# teensyMotors02_upSwitch_LED.net
KiCad netlist of a schematic drawn in EAGLE
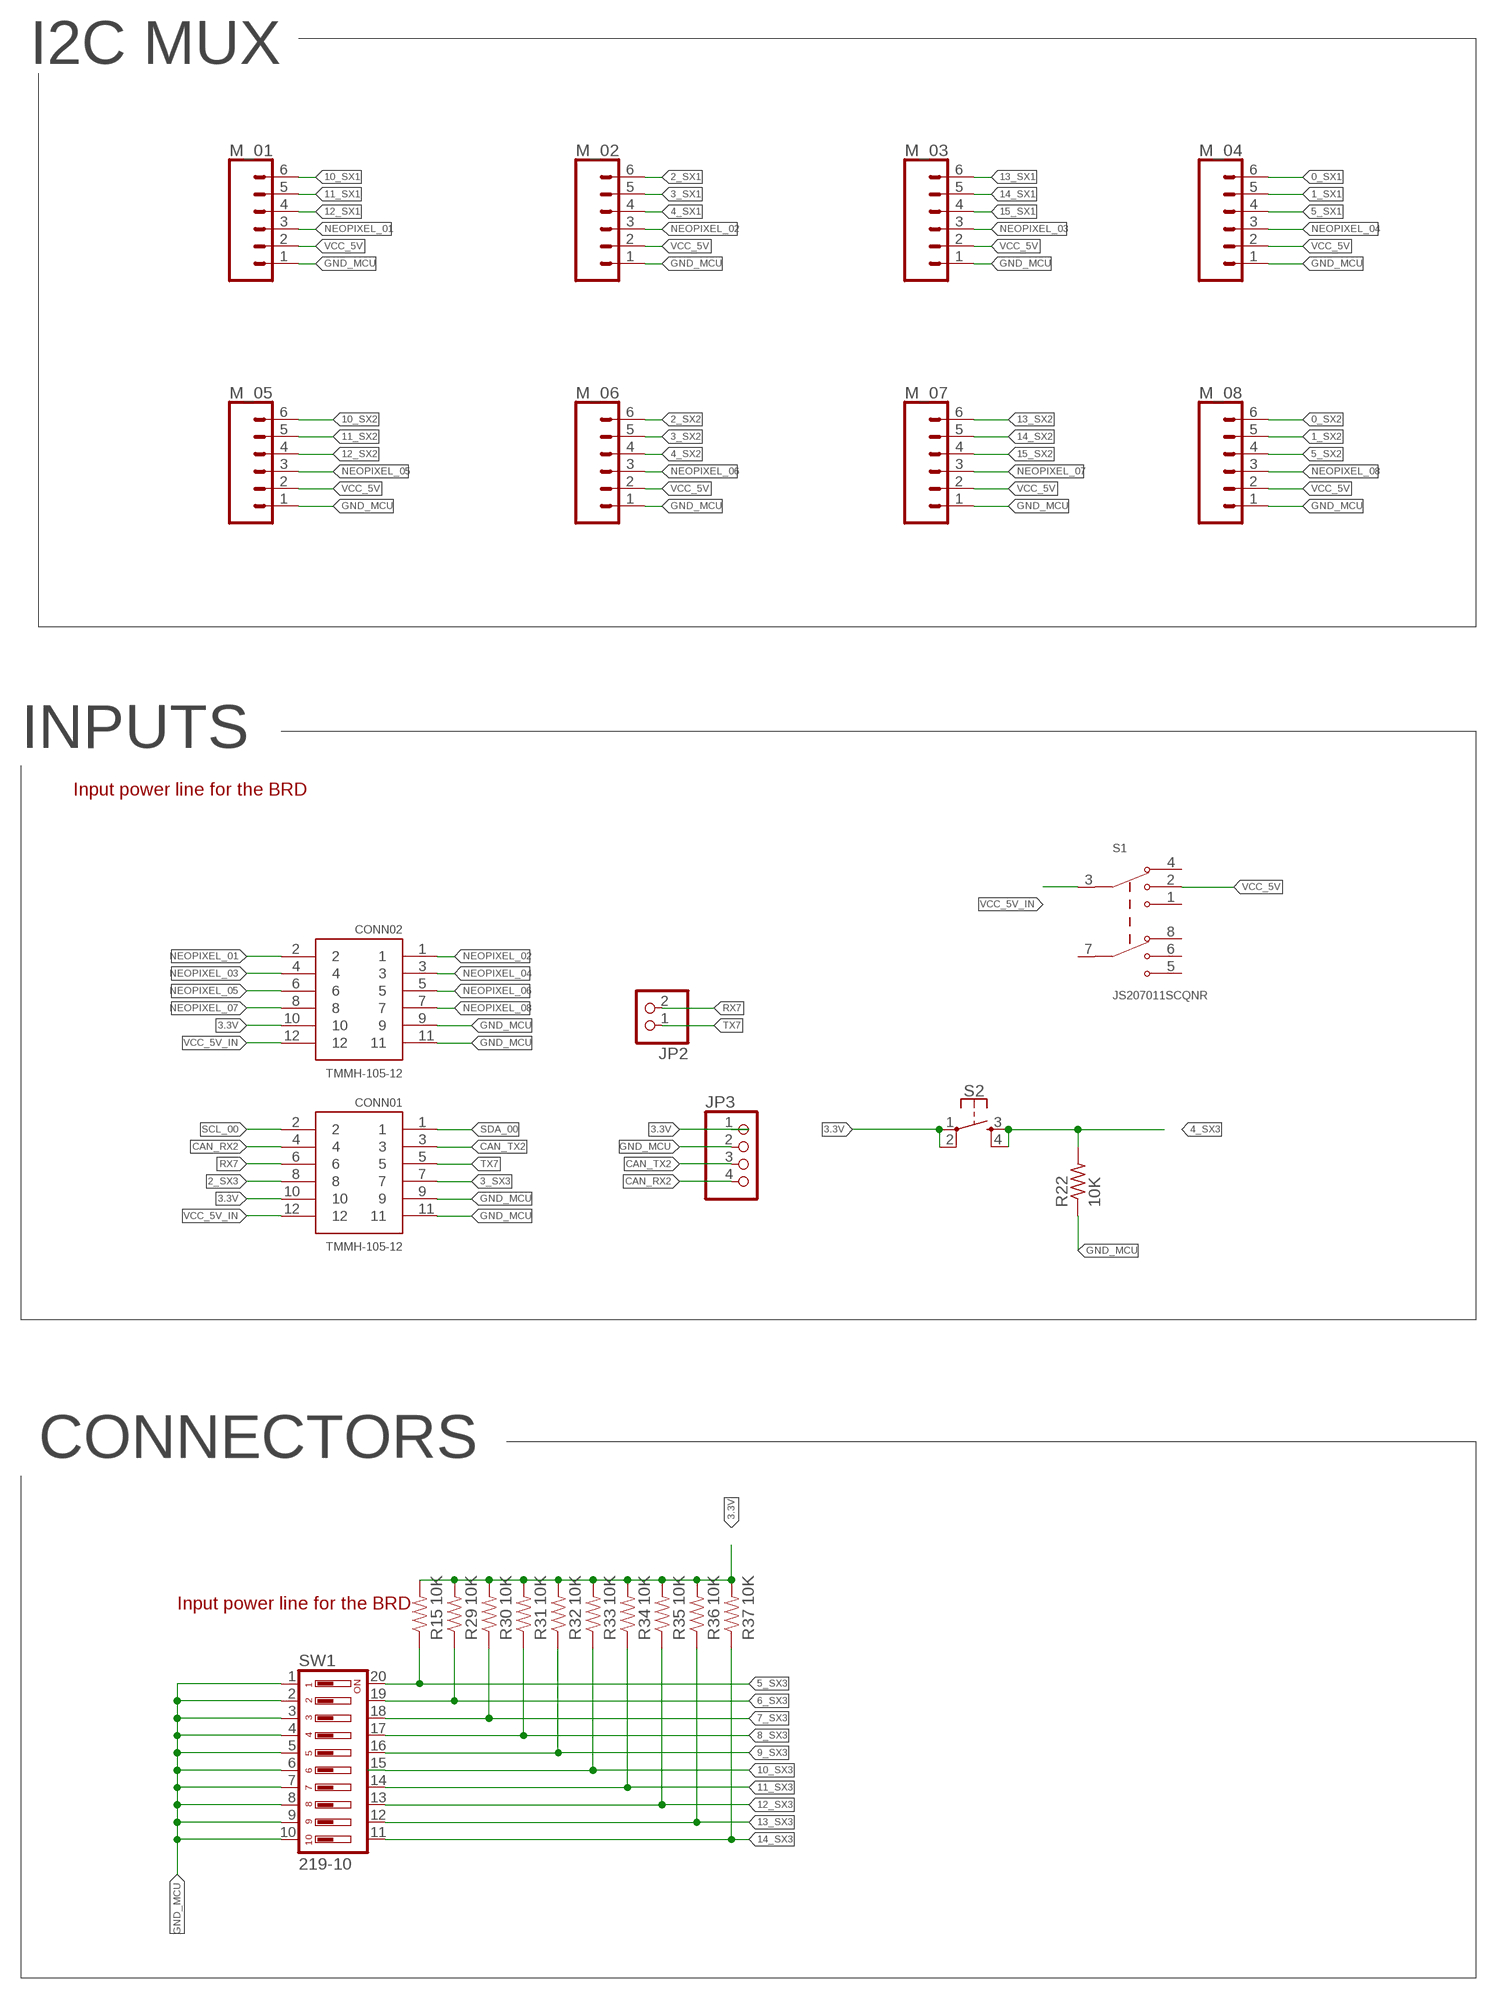
[diagram p0: schematic, sheet 1, part 1 of 3]
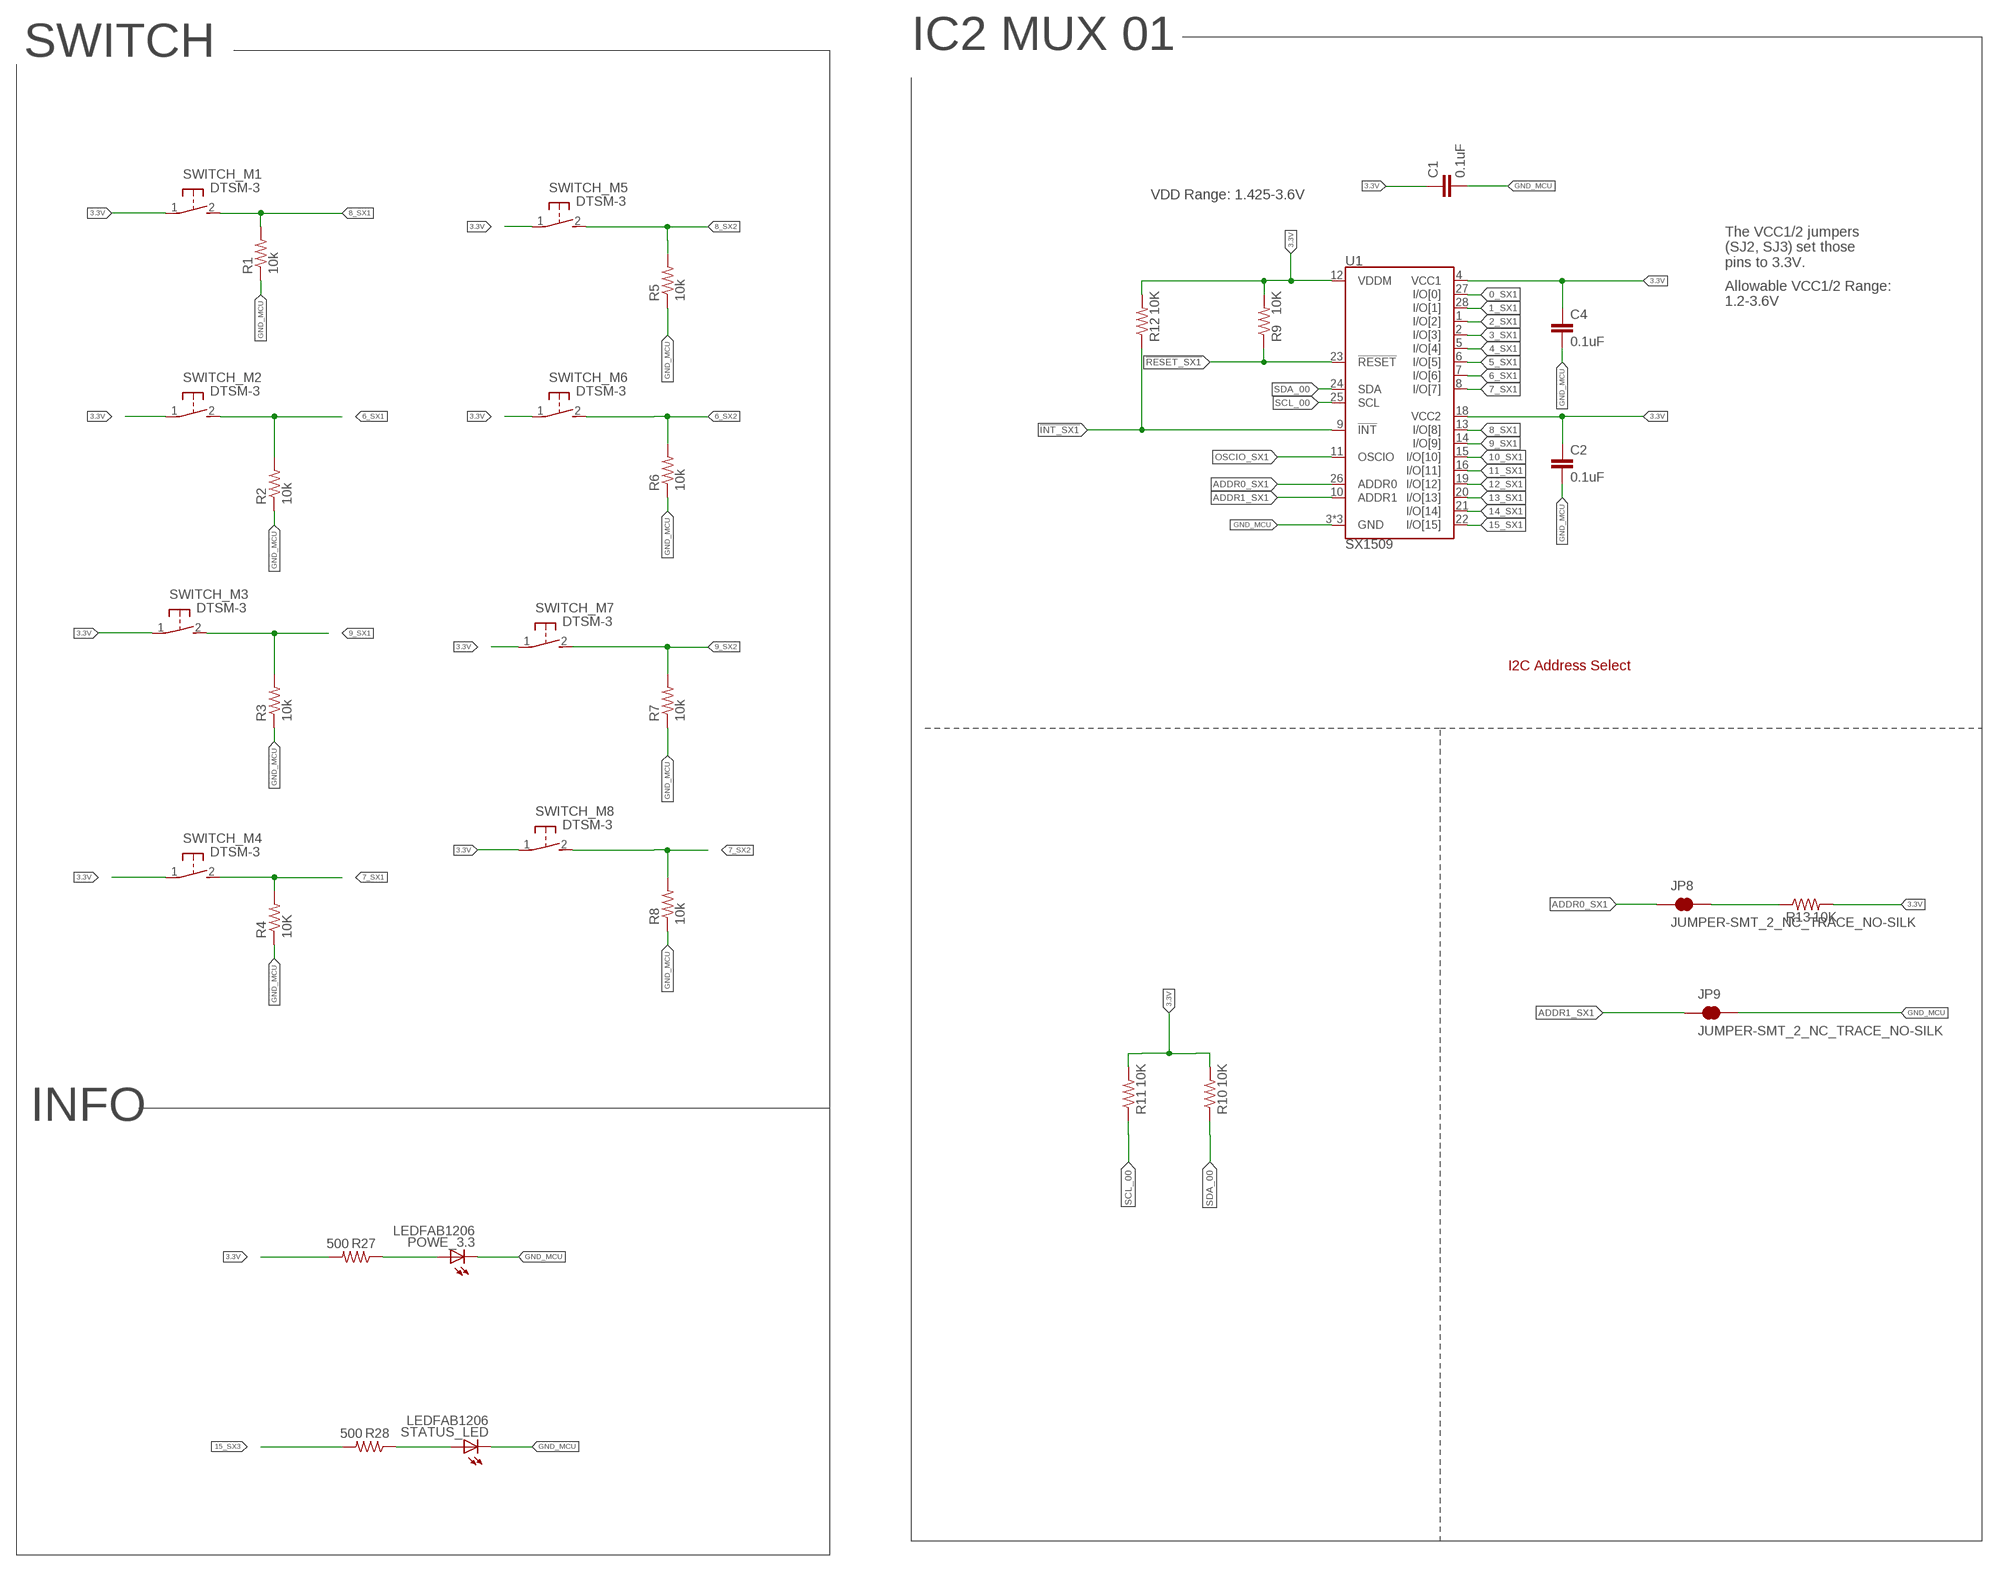
[diagram p1: schematic, sheet 1, part 2 of 3]
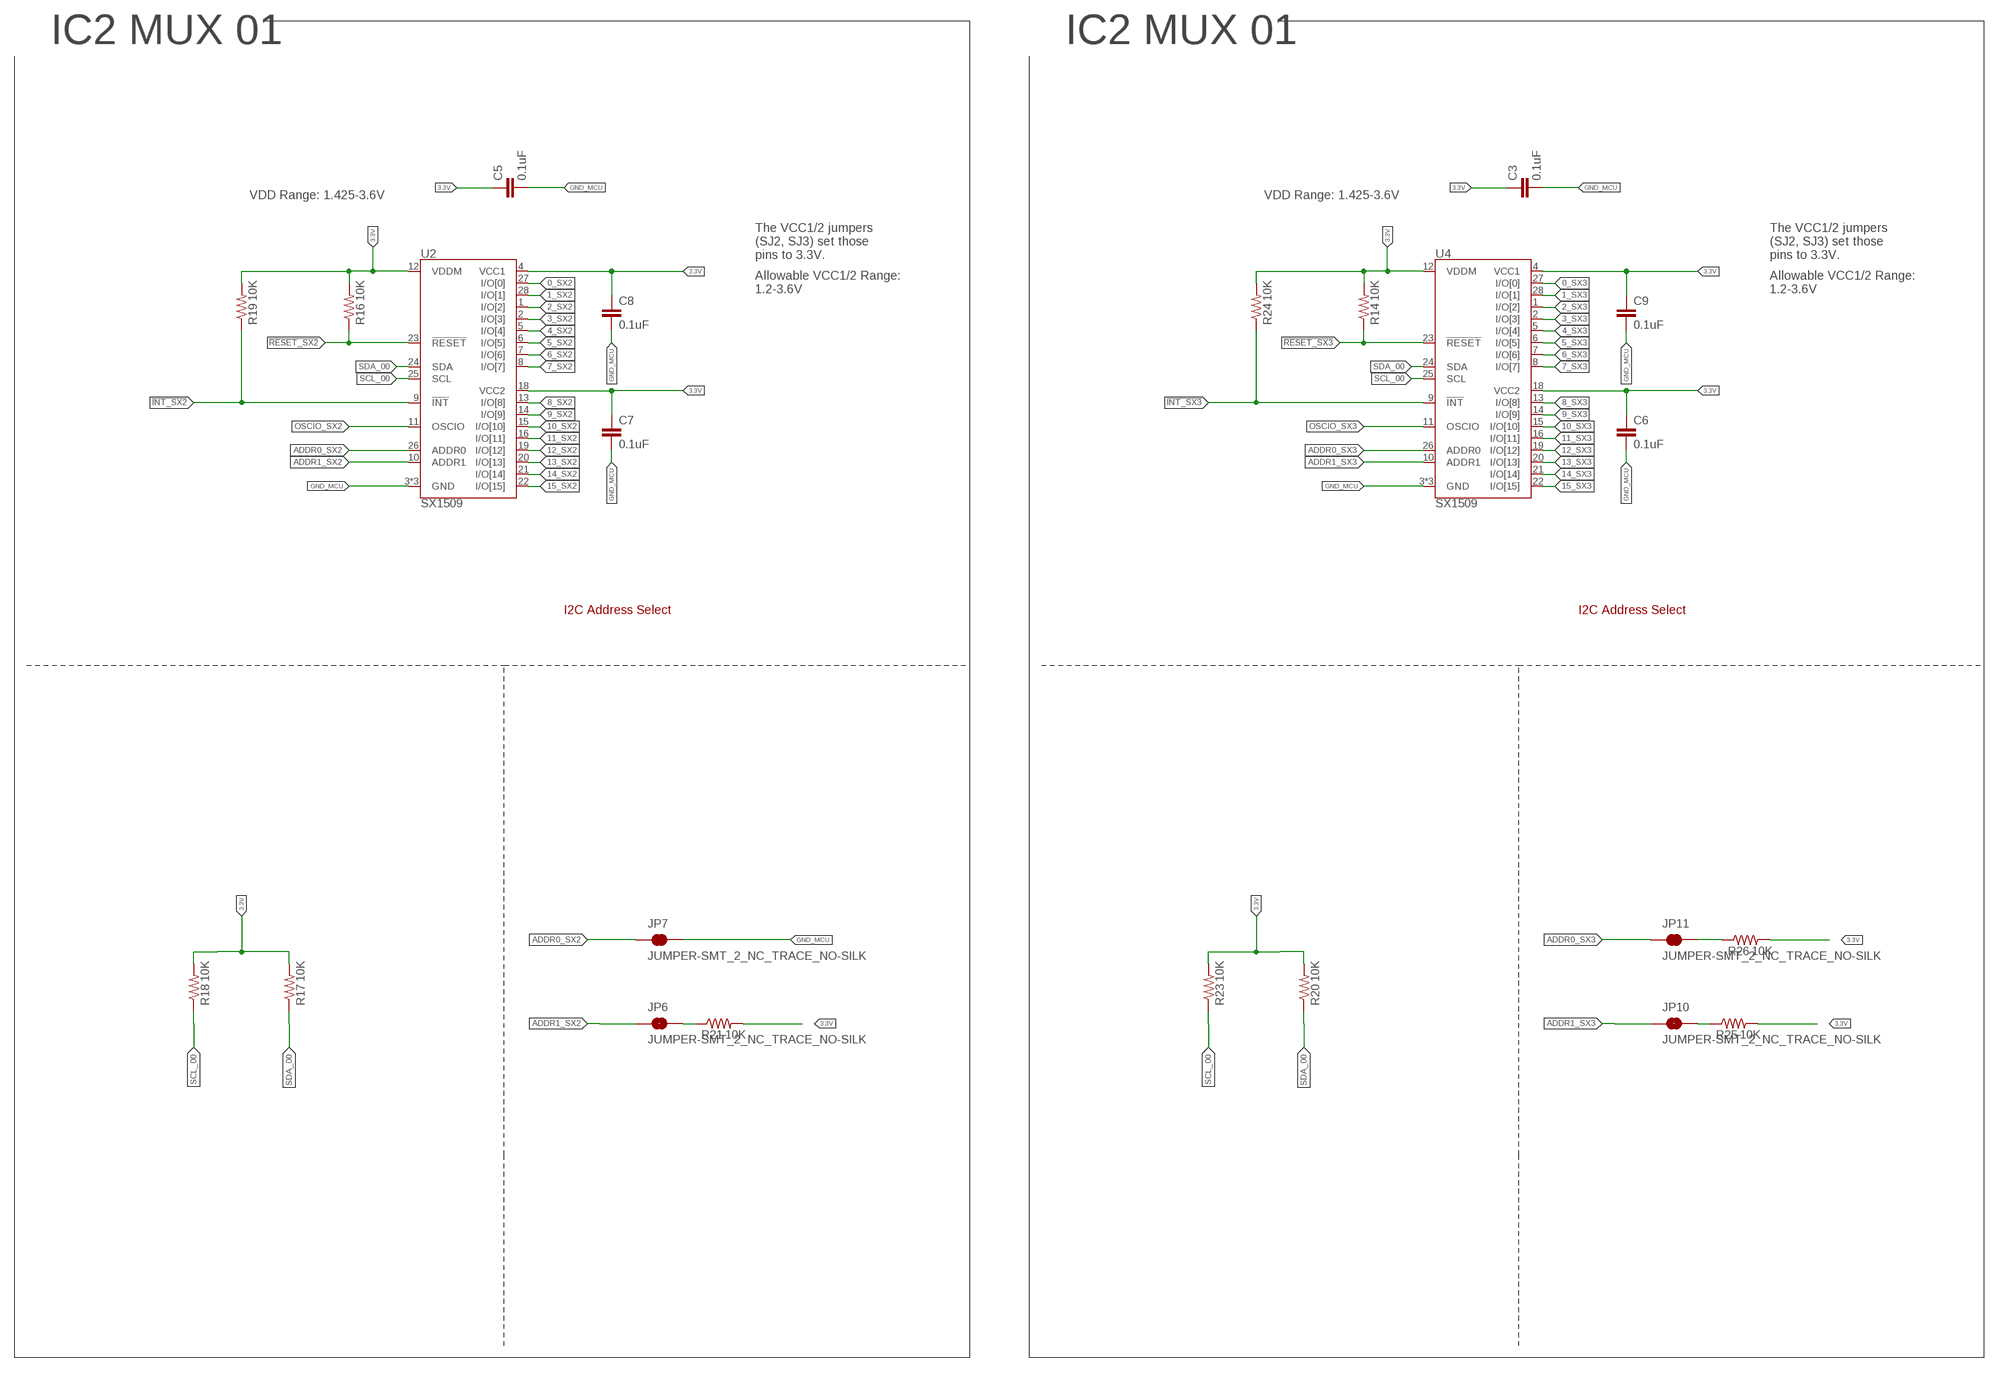
[diagram p2: schematic, sheet 1, part 3 of 3]

(export (version "E")
  (design (tool "Eeschema 10.0.6"))
  (components
    (comp (ref "C1")
      (value "0.1uF")
      (footprint "eagle-import:0603-CAP")
      (libsource (lib "eagle-import") (part "0.1UF-25V(+80/-20%)(0603)"))
    )
    (comp (ref "C2")
      (value "0.1uF")
      (footprint "eagle-import:0603-CAP")
      (libsource (lib "eagle-import") (part "0.1UF-25V(+80/-20%)(0603)"))
    )
    (comp (ref "C3")
      (value "0.1uF")
      (footprint "eagle-import:0603-CAP")
      (libsource (lib "eagle-import") (part "0.1UF-25V(+80/-20%)(0603)"))
    )
    (comp (ref "C4")
      (value "0.1uF")
      (footprint "eagle-import:0603-CAP")
      (libsource (lib "eagle-import") (part "0.1UF-25V(+80/-20%)(0603)"))
    )
    (comp (ref "C5")
      (value "0.1uF")
      (footprint "eagle-import:0603-CAP")
      (libsource (lib "eagle-import") (part "0.1UF-25V(+80/-20%)(0603)"))
    )
    (comp (ref "C6")
      (value "0.1uF")
      (footprint "eagle-import:0603-CAP")
      (libsource (lib "eagle-import") (part "0.1UF-25V(+80/-20%)(0603)"))
    )
    (comp (ref "C7")
      (value "0.1uF")
      (footprint "eagle-import:0603-CAP")
      (libsource (lib "eagle-import") (part "0.1UF-25V(+80/-20%)(0603)"))
    )
    (comp (ref "C8")
      (value "0.1uF")
      (footprint "eagle-import:0603-CAP")
      (libsource (lib "eagle-import") (part "0.1UF-25V(+80/-20%)(0603)"))
    )
    (comp (ref "C9")
      (value "0.1uF")
      (footprint "eagle-import:0603-CAP")
      (libsource (lib "eagle-import") (part "0.1UF-25V(+80/-20%)(0603)"))
    )
    (comp (ref "CONN01")
      (value "TMMH-105-12")
      (footprint "eagle-import:TMMH-105-12")
      (libsource (lib "eagle-import") (part "TMMH-105-12"))
    )
    (comp (ref "CONN02")
      (value "TMMH-105-12")
      (footprint "eagle-import:TMMH-105-12")
      (libsource (lib "eagle-import") (part "TMMH-105-12"))
    )
    (comp (ref "JP2")
      (value "HEADER-1X2ROUND")
      (footprint "eagle-import:1X02_ROUND")
      (libsource (lib "eagle-import") (part "HEADER-1X2ROUND"))
    )
    (comp (ref "JP3")
      (value "HEADER-1X4ROUND")
      (footprint "eagle-import:1X04_ROUND")
      (libsource (lib "eagle-import") (part "HEADER-1X4ROUND"))
    )
    (comp (ref "JP6")
      (value "JUMPER-SMT_2_NC_TRACE_NO-SILK")
      (footprint "eagle-import:SMT-JUMPER_2_NC_TRACE_NO-SILK")
      (libsource (lib "eagle-import") (part "JUMPER-SMT_2_NC_TRACE_NO-SILK"))
    )
    (comp (ref "JP7")
      (value "JUMPER-SMT_2_NC_TRACE_NO-SILK")
      (footprint "eagle-import:SMT-JUMPER_2_NC_TRACE_NO-SILK")
      (libsource (lib "eagle-import") (part "JUMPER-SMT_2_NC_TRACE_NO-SILK"))
    )
    (comp (ref "JP8")
      (value "JUMPER-SMT_2_NC_TRACE_NO-SILK")
      (footprint "eagle-import:SMT-JUMPER_2_NC_TRACE_NO-SILK")
      (libsource (lib "eagle-import") (part "JUMPER-SMT_2_NC_TRACE_NO-SILK"))
    )
    (comp (ref "JP9")
      (value "JUMPER-SMT_2_NC_TRACE_NO-SILK")
      (footprint "eagle-import:SMT-JUMPER_2_NC_TRACE_NO-SILK")
      (libsource (lib "eagle-import") (part "JUMPER-SMT_2_NC_TRACE_NO-SILK"))
    )
    (comp (ref "JP10")
      (value "JUMPER-SMT_2_NC_TRACE_NO-SILK")
      (footprint "eagle-import:SMT-JUMPER_2_NC_TRACE_NO-SILK")
      (libsource (lib "eagle-import") (part "JUMPER-SMT_2_NC_TRACE_NO-SILK"))
    )
    (comp (ref "JP11")
      (value "JUMPER-SMT_2_NC_TRACE_NO-SILK")
      (footprint "eagle-import:SMT-JUMPER_2_NC_TRACE_NO-SILK")
      (libsource (lib "eagle-import") (part "JUMPER-SMT_2_NC_TRACE_NO-SILK"))
    )
    (comp (ref "M_01")
      (value "CONN_06SMD-1MM")
      (footprint "eagle-import:1X06-1MM")
      (libsource (lib "eagle-import") (part "CONN_06SMD-1MM"))
    )
    (comp (ref "M_02")
      (value "CONN_06SMD-1MM")
      (footprint "eagle-import:1X06-1MM")
      (libsource (lib "eagle-import") (part "CONN_06SMD-1MM"))
    )
    (comp (ref "M_03")
      (value "CONN_06SMD-1MM")
      (footprint "eagle-import:1X06-1MM")
      (libsource (lib "eagle-import") (part "CONN_06SMD-1MM"))
    )
    (comp (ref "M_04")
      (value "CONN_06SMD-1MM")
      (footprint "eagle-import:1X06-1MM")
      (libsource (lib "eagle-import") (part "CONN_06SMD-1MM"))
    )
    (comp (ref "M_05")
      (value "CONN_06SMD-1MM")
      (footprint "eagle-import:1X06-1MM")
      (libsource (lib "eagle-import") (part "CONN_06SMD-1MM"))
    )
    (comp (ref "M_06")
      (value "CONN_06SMD-1MM")
      (footprint "eagle-import:1X06-1MM")
      (libsource (lib "eagle-import") (part "CONN_06SMD-1MM"))
    )
    (comp (ref "M_07")
      (value "CONN_06SMD-1MM")
      (footprint "eagle-import:1X06-1MM")
      (libsource (lib "eagle-import") (part "CONN_06SMD-1MM"))
    )
    (comp (ref "M_08")
      (value "CONN_06SMD-1MM")
      (footprint "eagle-import:1X06-1MM")
      (libsource (lib "eagle-import") (part "CONN_06SMD-1MM"))
    )
    (comp (ref "POWE_3.3")
      (value "LEDFAB1206")
      (footprint "eagle-import:LED1206FAB")
      (libsource (lib "eagle-import") (part "LEDFAB1206"))
    )
    (comp (ref "R1")
      (value "10k")
      (footprint "eagle-import:M0805")
      (libsource (lib "eagle-import") (part "R-US_M0805"))
    )
    (comp (ref "R2")
      (value "10k")
      (footprint "eagle-import:M0805")
      (libsource (lib "eagle-import") (part "R-US_M0805"))
    )
    (comp (ref "R3")
      (value "10k")
      (footprint "eagle-import:M0805")
      (libsource (lib "eagle-import") (part "R-US_M0805"))
    )
    (comp (ref "R4")
      (value "10K")
      (footprint "eagle-import:M0805")
      (libsource (lib "eagle-import") (part "R-US_M0805"))
    )
    (comp (ref "R5")
      (value "10k")
      (footprint "eagle-import:M0805")
      (libsource (lib "eagle-import") (part "R-US_M0805"))
    )
    (comp (ref "R6")
      (value "10k")
      (footprint "eagle-import:M0805")
      (libsource (lib "eagle-import") (part "R-US_M0805"))
    )
    (comp (ref "R7")
      (value "10k")
      (footprint "eagle-import:M0805")
      (libsource (lib "eagle-import") (part "R-US_M0805"))
    )
    (comp (ref "R8")
      (value "10k")
      (footprint "eagle-import:M0805")
      (libsource (lib "eagle-import") (part "R-US_M0805"))
    )
    (comp (ref "R9")
      (value "10K")
      (footprint "eagle-import:0603-RES")
      (libsource (lib "eagle-import") (part "SparkFun-Resistors_532_10KOHM-1/10W-1%(0603)0603"))
    )
    (comp (ref "R10")
      (value "10K")
      (footprint "eagle-import:0603-RES")
      (libsource (lib "eagle-import") (part "SparkFun-Resistors_532_10KOHM-1/10W-1%(0603)0603"))
    )
    (comp (ref "R11")
      (value "10K")
      (footprint "eagle-import:0603-RES")
      (libsource (lib "eagle-import") (part "SparkFun-Resistors_532_10KOHM-1/10W-1%(0603)0603"))
    )
    (comp (ref "R12")
      (value "10K")
      (footprint "eagle-import:0603-RES")
      (libsource (lib "eagle-import") (part "SparkFun-Resistors_532_10KOHM-1/10W-1%(0603)0603"))
    )
    (comp (ref "R13")
      (value "10K")
      (footprint "eagle-import:0603-RES")
      (libsource (lib "eagle-import") (part "SparkFun-Resistors_532_10KOHM-1/10W-1%(0603)0603"))
    )
    (comp (ref "R14")
      (value "10K")
      (footprint "eagle-import:0603-RES")
      (libsource (lib "eagle-import") (part "SparkFun-Resistors_532_10KOHM-1/10W-1%(0603)0603"))
    )
    (comp (ref "R15")
      (value "10K")
      (footprint "eagle-import:0603-RES")
      (libsource (lib "eagle-import") (part "SparkFun-Resistors_532_10KOHM-1/10W-1%(0603)0603"))
    )
    (comp (ref "R16")
      (value "10K")
      (footprint "eagle-import:0603-RES")
      (libsource (lib "eagle-import") (part "SparkFun-Resistors_532_10KOHM-1/10W-1%(0603)0603"))
    )
    (comp (ref "R17")
      (value "10K")
      (footprint "eagle-import:0603-RES")
      (libsource (lib "eagle-import") (part "SparkFun-Resistors_532_10KOHM-1/10W-1%(0603)0603"))
    )
    (comp (ref "R18")
      (value "10K")
      (footprint "eagle-import:0603-RES")
      (libsource (lib "eagle-import") (part "SparkFun-Resistors_532_10KOHM-1/10W-1%(0603)0603"))
    )
    (comp (ref "R19")
      (value "10K")
      (footprint "eagle-import:0603-RES")
      (libsource (lib "eagle-import") (part "SparkFun-Resistors_532_10KOHM-1/10W-1%(0603)0603"))
    )
    (comp (ref "R20")
      (value "10K")
      (footprint "eagle-import:0603-RES")
      (libsource (lib "eagle-import") (part "SparkFun-Resistors_532_10KOHM-1/10W-1%(0603)0603"))
    )
    (comp (ref "R21")
      (value "10K")
      (footprint "eagle-import:0603-RES")
      (libsource (lib "eagle-import") (part "SparkFun-Resistors_532_10KOHM-1/10W-1%(0603)0603"))
    )
    (comp (ref "R22")
      (value "10K")
      (footprint "eagle-import:M0805")
      (libsource (lib "eagle-import") (part "R-US_M0805"))
    )
    (comp (ref "R23")
      (value "10K")
      (footprint "eagle-import:0603-RES")
      (libsource (lib "eagle-import") (part "SparkFun-Resistors_532_10KOHM-1/10W-1%(0603)0603"))
    )
    (comp (ref "R24")
      (value "10K")
      (footprint "eagle-import:0603-RES")
      (libsource (lib "eagle-import") (part "SparkFun-Resistors_532_10KOHM-1/10W-1%(0603)0603"))
    )
    (comp (ref "R25")
      (value "10K")
      (footprint "eagle-import:0603-RES")
      (libsource (lib "eagle-import") (part "SparkFun-Resistors_532_10KOHM-1/10W-1%(0603)0603"))
    )
    (comp (ref "R26")
      (value "10K")
      (footprint "eagle-import:0603-RES")
      (libsource (lib "eagle-import") (part "SparkFun-Resistors_532_10KOHM-1/10W-1%(0603)0603"))
    )
    (comp (ref "R27")
      (value "500")
      (footprint "eagle-import:0603-RES")
      (libsource (lib "eagle-import") (part "10KOHM-1/10W-1%(0603)0603"))
    )
    (comp (ref "R28")
      (value "500")
      (footprint "eagle-import:0603-RES")
      (libsource (lib "eagle-import") (part "10KOHM-1/10W-1%(0603)0603"))
    )
    (comp (ref "R29")
      (value "10K")
      (footprint "eagle-import:0603-RES")
      (libsource (lib "eagle-import") (part "SparkFun-Resistors_532_10KOHM-1/10W-1%(0603)0603"))
    )
    (comp (ref "R30")
      (value "10K")
      (footprint "eagle-import:0603-RES")
      (libsource (lib "eagle-import") (part "SparkFun-Resistors_532_10KOHM-1/10W-1%(0603)0603"))
    )
    (comp (ref "R31")
      (value "10K")
      (footprint "eagle-import:0603-RES")
      (libsource (lib "eagle-import") (part "SparkFun-Resistors_532_10KOHM-1/10W-1%(0603)0603"))
    )
    (comp (ref "R32")
      (value "10K")
      (footprint "eagle-import:0603-RES")
      (libsource (lib "eagle-import") (part "SparkFun-Resistors_532_10KOHM-1/10W-1%(0603)0603"))
    )
    (comp (ref "R33")
      (value "10K")
      (footprint "eagle-import:0603-RES")
      (libsource (lib "eagle-import") (part "SparkFun-Resistors_532_10KOHM-1/10W-1%(0603)0603"))
    )
    (comp (ref "R34")
      (value "10K")
      (footprint "eagle-import:0603-RES")
      (libsource (lib "eagle-import") (part "SparkFun-Resistors_532_10KOHM-1/10W-1%(0603)0603"))
    )
    (comp (ref "R35")
      (value "10K")
      (footprint "eagle-import:0603-RES")
      (libsource (lib "eagle-import") (part "SparkFun-Resistors_532_10KOHM-1/10W-1%(0603)0603"))
    )
    (comp (ref "R36")
      (value "10K")
      (footprint "eagle-import:0603-RES")
      (libsource (lib "eagle-import") (part "SparkFun-Resistors_532_10KOHM-1/10W-1%(0603)0603"))
    )
    (comp (ref "R37")
      (value "10K")
      (footprint "eagle-import:0603-RES")
      (libsource (lib "eagle-import") (part "SparkFun-Resistors_532_10KOHM-1/10W-1%(0603)0603"))
    )
    (comp (ref "S1")
      (value "JS207011SCQNR")
      (footprint "eagle-import:SW_JS207011SCQNR")
      (fields (field (name "MF") "C&K"))
      (libsource (lib "eagle-import") (part "JS207011SCQNR"))
    )
    (comp (ref "S2")
      (value "MOMENTARY-SWITCH-SPST-2-SMD-5.2MM")
      (footprint "eagle-import:TACTILE_SWITCH_SMD_5.2MM")
      (libsource (lib "eagle-import") (part "MOMENTARY-SWITCH-SPST-2-SMD-5.2MM"))
    )
    (comp (ref "STATUS_LED")
      (value "LEDFAB1206")
      (footprint "eagle-import:LED1206FAB")
      (libsource (lib "eagle-import") (part "LEDFAB1206"))
    )
    (comp (ref "SW1")
      (value "219-10")
      (footprint "eagle-import:CTS-219-10")
      (fields (field (name "MF") "SLI (CML/IDI)") (field (name "MPN") "219-10PK"))
      (libsource (lib "eagle-import") (part "219-10"))
    )
    (comp (ref "SWITCH_M1")
      (value "DTSM-3")
      (footprint "eagle-import:DTSM-3")
      (libsource (lib "eagle-import") (part "DTSM-3"))
    )
    (comp (ref "SWITCH_M2")
      (value "DTSM-3")
      (footprint "eagle-import:DTSM-3")
      (libsource (lib "eagle-import") (part "DTSM-3"))
    )
    (comp (ref "SWITCH_M3")
      (value "DTSM-3")
      (footprint "eagle-import:DTSM-3")
      (libsource (lib "eagle-import") (part "DTSM-3"))
    )
    (comp (ref "SWITCH_M4")
      (value "DTSM-3")
      (footprint "eagle-import:DTSM-3")
      (libsource (lib "eagle-import") (part "DTSM-3"))
    )
    (comp (ref "SWITCH_M5")
      (value "DTSM-3")
      (footprint "eagle-import:DTSM-3")
      (libsource (lib "eagle-import") (part "DTSM-3"))
    )
    (comp (ref "SWITCH_M6")
      (value "DTSM-3")
      (footprint "eagle-import:DTSM-3")
      (libsource (lib "eagle-import") (part "DTSM-3"))
    )
    (comp (ref "SWITCH_M7")
      (value "DTSM-3")
      (footprint "eagle-import:DTSM-3")
      (libsource (lib "eagle-import") (part "DTSM-3"))
    )
    (comp (ref "SWITCH_M8")
      (value "DTSM-3")
      (footprint "eagle-import:DTSM-3")
      (libsource (lib "eagle-import") (part "DTSM-3"))
    )
    (comp (ref "U1")
      (value "SX1509")
      (footprint "eagle-import:QFN-28")
      (libsource (lib "eagle-import") (part "SX1509"))
    )
    (comp (ref "U2")
      (value "SX1509")
      (footprint "eagle-import:QFN-28")
      (libsource (lib "eagle-import") (part "SX1509"))
    )
    (comp (ref "U4")
      (value "SX1509")
      (footprint "eagle-import:QFN-28")
      (libsource (lib "eagle-import") (part "SX1509"))
    )
  )
  (nets
    (net (code "1") (name "/~{INT_SX1}") (class "Default")
      (node (ref "R12") (pin "1") (pinfunction "1_1") (pintype "passive"))
      (node (ref "U1") (pin "9") (pinfunction "~{INT}_9") (pintype "bidirectional"))
    )
    (net (code "2") (name "/~{INT_SX2}") (class "Default")
      (node (ref "R19") (pin "1") (pinfunction "1_1") (pintype "passive"))
      (node (ref "U2") (pin "9") (pinfunction "~{INT}_9") (pintype "bidirectional"))
    )
    (net (code "3") (name "/~{INT_SX3}") (class "Default")
      (node (ref "R24") (pin "1") (pinfunction "1_1") (pintype "passive"))
      (node (ref "U4") (pin "9") (pinfunction "~{INT}_9") (pintype "bidirectional"))
    )
    (net (code "4") (name "/~{RESET_SX1}") (class "Default")
      (node (ref "R9") (pin "1") (pinfunction "1_1") (pintype "passive"))
      (node (ref "U1") (pin "23") (pinfunction "~{RESET}_23") (pintype "bidirectional"))
    )
    (net (code "5") (name "/~{RESET_SX2}") (class "Default")
      (node (ref "R16") (pin "1") (pinfunction "1_1") (pintype "passive"))
      (node (ref "U2") (pin "23") (pinfunction "~{RESET}_23") (pintype "bidirectional"))
    )
    (net (code "6") (name "/~{RESET_SX3}") (class "Default")
      (node (ref "R14") (pin "1") (pinfunction "1_1") (pintype "passive"))
      (node (ref "U4") (pin "23") (pinfunction "~{RESET}_23") (pintype "bidirectional"))
    )
    (net (code "7") (name "0_SX1") (class "Default")
      (node (ref "M_04") (pin "6") (pinfunction "6_6") (pintype "passive"))
      (node (ref "U1") (pin "27") (pinfunction "I/O[0]_27") (pintype "bidirectional"))
    )
    (net (code "8") (name "0_SX2") (class "Default")
      (node (ref "M_08") (pin "6") (pinfunction "6_6") (pintype "passive"))
      (node (ref "U2") (pin "27") (pinfunction "I/O[0]_27") (pintype "bidirectional"))
    )
    (net (code "9") (name "0_SX3") (class "Default")
      (node (ref "U4") (pin "27") (pinfunction "I/O[0]_27") (pintype "bidirectional"))
    )
    (net (code "10") (name "1_SX1") (class "Default")
      (node (ref "M_04") (pin "5") (pinfunction "5_5") (pintype "passive"))
      (node (ref "U1") (pin "28") (pinfunction "I/O[1]_28") (pintype "bidirectional"))
    )
    (net (code "11") (name "1_SX2") (class "Default")
      (node (ref "M_08") (pin "5") (pinfunction "5_5") (pintype "passive"))
      (node (ref "U2") (pin "28") (pinfunction "I/O[1]_28") (pintype "bidirectional"))
    )
    (net (code "12") (name "1_SX3") (class "Default")
      (node (ref "U4") (pin "28") (pinfunction "I/O[1]_28") (pintype "bidirectional"))
    )
    (net (code "13") (name "2_SX1") (class "Default")
      (node (ref "M_02") (pin "6") (pinfunction "6_6") (pintype "passive"))
      (node (ref "U1") (pin "1") (pinfunction "I/O[2]_1") (pintype "bidirectional"))
    )
    (net (code "14") (name "2_SX2") (class "Default")
      (node (ref "M_06") (pin "6") (pinfunction "6_6") (pintype "passive"))
      (node (ref "U2") (pin "1") (pinfunction "I/O[2]_1") (pintype "bidirectional"))
    )
    (net (code "15") (name "2_SX3") (class "Default")
      (node (ref "CONN01") (pin "8") (pinfunction "8_8") (pintype "bidirectional"))
      (node (ref "U4") (pin "1") (pinfunction "I/O[2]_1") (pintype "bidirectional"))
    )
    (net (code "16") (name "3.3V") (class "Default")
      (node (ref "C1") (pin "1") (pinfunction "1_1") (pintype "passive"))
      (node (ref "C2") (pin "1") (pinfunction "1_1") (pintype "passive"))
      (node (ref "C3") (pin "1") (pinfunction "1_1") (pintype "passive"))
      (node (ref "C4") (pin "1") (pinfunction "1_1") (pintype "passive"))
      (node (ref "C5") (pin "1") (pinfunction "1_1") (pintype "passive"))
      (node (ref "C6") (pin "1") (pinfunction "1_1") (pintype "passive"))
      (node (ref "C7") (pin "1") (pinfunction "1_1") (pintype "passive"))
      (node (ref "C8") (pin "1") (pinfunction "1_1") (pintype "passive"))
      (node (ref "C9") (pin "1") (pinfunction "1_1") (pintype "passive"))
      (node (ref "CONN01") (pin "10") (pinfunction "10_10") (pintype "bidirectional"))
      (node (ref "CONN02") (pin "10") (pinfunction "10_10") (pintype "bidirectional"))
      (node (ref "JP3") (pin "1") (pinfunction "1_1") (pintype "passive"))
      (node (ref "R10") (pin "2") (pinfunction "2_2") (pintype "passive"))
      (node (ref "R11") (pin "2") (pinfunction "2_2") (pintype "passive"))
      (node (ref "R12") (pin "2") (pinfunction "2_2") (pintype "passive"))
      (node (ref "R13") (pin "2") (pinfunction "2_2") (pintype "passive"))
      (node (ref "R14") (pin "2") (pinfunction "2_2") (pintype "passive"))
      (node (ref "R15") (pin "2") (pinfunction "2_2") (pintype "passive"))
      (node (ref "R16") (pin "2") (pinfunction "2_2") (pintype "passive"))
      (node (ref "R17") (pin "2") (pinfunction "2_2") (pintype "passive"))
      (node (ref "R18") (pin "2") (pinfunction "2_2") (pintype "passive"))
      (node (ref "R19") (pin "2") (pinfunction "2_2") (pintype "passive"))
      (node (ref "R20") (pin "2") (pinfunction "2_2") (pintype "passive"))
      (node (ref "R21") (pin "2") (pinfunction "2_2") (pintype "passive"))
      (node (ref "R23") (pin "2") (pinfunction "2_2") (pintype "passive"))
      (node (ref "R24") (pin "2") (pinfunction "2_2") (pintype "passive"))
      (node (ref "R25") (pin "2") (pinfunction "2_2") (pintype "passive"))
      (node (ref "R26") (pin "2") (pinfunction "2_2") (pintype "passive"))
      (node (ref "R27") (pin "2") (pinfunction "2_2") (pintype "passive"))
      (node (ref "R29") (pin "2") (pinfunction "2_2") (pintype "passive"))
      (node (ref "R30") (pin "2") (pinfunction "2_2") (pintype "passive"))
      (node (ref "R31") (pin "2") (pinfunction "2_2") (pintype "passive"))
      (node (ref "R32") (pin "2") (pinfunction "2_2") (pintype "passive"))
      (node (ref "R33") (pin "2") (pinfunction "2_2") (pintype "passive"))
      (node (ref "R34") (pin "2") (pinfunction "2_2") (pintype "passive"))
      (node (ref "R35") (pin "2") (pinfunction "2_2") (pintype "passive"))
      (node (ref "R36") (pin "2") (pinfunction "2_2") (pintype "passive"))
      (node (ref "R37") (pin "2") (pinfunction "2_2") (pintype "passive"))
      (node (ref "R9") (pin "2") (pinfunction "2_2") (pintype "passive"))
      (node (ref "S2") (pin "1") (pinfunction "1_1") (pintype "passive"))
      (node (ref "S2") (pin "2") (pinfunction "2_2") (pintype "passive"))
      (node (ref "SWITCH_M1") (pin "1") (pinfunction "1_1") (pintype "passive"))
      (node (ref "SWITCH_M2") (pin "1") (pinfunction "1_1") (pintype "passive"))
      (node (ref "SWITCH_M3") (pin "1") (pinfunction "1_1") (pintype "passive"))
      (node (ref "SWITCH_M4") (pin "1") (pinfunction "1_1") (pintype "passive"))
      (node (ref "SWITCH_M5") (pin "1") (pinfunction "1_1") (pintype "passive"))
      (node (ref "SWITCH_M6") (pin "1") (pinfunction "1_1") (pintype "passive"))
      (node (ref "SWITCH_M7") (pin "1") (pinfunction "1_1") (pintype "passive"))
      (node (ref "SWITCH_M8") (pin "1") (pinfunction "1_1") (pintype "passive"))
      (node (ref "U1") (pin "12") (pinfunction "VDDM_12") (pintype "bidirectional"))
      (node (ref "U1") (pin "18") (pinfunction "VCC2_18") (pintype "bidirectional"))
      (node (ref "U1") (pin "4") (pinfunction "VCC1_4") (pintype "bidirectional"))
      (node (ref "U2") (pin "12") (pinfunction "VDDM_12") (pintype "bidirectional"))
      (node (ref "U2") (pin "18") (pinfunction "VCC2_18") (pintype "bidirectional"))
      (node (ref "U2") (pin "4") (pinfunction "VCC1_4") (pintype "bidirectional"))
      (node (ref "U4") (pin "12") (pinfunction "VDDM_12") (pintype "bidirectional"))
      (node (ref "U4") (pin "18") (pinfunction "VCC2_18") (pintype "bidirectional"))
      (node (ref "U4") (pin "4") (pinfunction "VCC1_4") (pintype "bidirectional"))
    )
    (net (code "17") (name "3_SX1") (class "Default")
      (node (ref "M_02") (pin "5") (pinfunction "5_5") (pintype "passive"))
      (node (ref "U1") (pin "2") (pinfunction "I/O[3]_2") (pintype "bidirectional"))
    )
    (net (code "18") (name "3_SX2") (class "Default")
      (node (ref "M_06") (pin "5") (pinfunction "5_5") (pintype "passive"))
      (node (ref "U2") (pin "2") (pinfunction "I/O[3]_2") (pintype "bidirectional"))
    )
    (net (code "19") (name "3_SX3") (class "Default")
      (node (ref "CONN01") (pin "7") (pinfunction "7_7") (pintype "bidirectional"))
      (node (ref "U4") (pin "2") (pinfunction "I/O[3]_2") (pintype "bidirectional"))
    )
    (net (code "20") (name "4_SX1") (class "Default")
      (node (ref "M_02") (pin "4") (pinfunction "4_4") (pintype "passive"))
      (node (ref "U1") (pin "5") (pinfunction "I/O[4]_5") (pintype "bidirectional"))
    )
    (net (code "21") (name "4_SX2") (class "Default")
      (node (ref "M_06") (pin "4") (pinfunction "4_4") (pintype "passive"))
      (node (ref "U2") (pin "5") (pinfunction "I/O[4]_5") (pintype "bidirectional"))
    )
    (net (code "22") (name "4_SX3") (class "Default")
      (node (ref "R22") (pin "2") (pinfunction "2_2") (pintype "passive"))
      (node (ref "S2") (pin "3") (pinfunction "3_3") (pintype "passive"))
      (node (ref "S2") (pin "4") (pinfunction "4_4") (pintype "passive"))
      (node (ref "U4") (pin "5") (pinfunction "I/O[4]_5") (pintype "bidirectional"))
    )
    (net (code "23") (name "5_SX1") (class "Default")
      (node (ref "M_04") (pin "4") (pinfunction "4_4") (pintype "passive"))
      (node (ref "U1") (pin "6") (pinfunction "I/O[5]_6") (pintype "bidirectional"))
    )
    (net (code "24") (name "5_SX2") (class "Default")
      (node (ref "M_08") (pin "4") (pinfunction "4_4") (pintype "passive"))
      (node (ref "U2") (pin "6") (pinfunction "I/O[5]_6") (pintype "bidirectional"))
    )
    (net (code "25") (name "5_SX3") (class "Default")
      (node (ref "R15") (pin "1") (pinfunction "1_1") (pintype "passive"))
      (node (ref "SW1") (pin "20") (pinfunction "20_20") (pintype "passive"))
      (node (ref "U4") (pin "6") (pinfunction "I/O[5]_6") (pintype "bidirectional"))
    )
    (net (code "26") (name "6_SX1") (class "Default")
      (node (ref "R2") (pin "2") (pinfunction "2_2") (pintype "passive"))
      (node (ref "SWITCH_M2") (pin "2") (pinfunction "2_2") (pintype "passive"))
      (node (ref "U1") (pin "7") (pinfunction "I/O[6]_7") (pintype "bidirectional"))
    )
    (net (code "27") (name "6_SX2") (class "Default")
      (node (ref "R6") (pin "2") (pinfunction "2_2") (pintype "passive"))
      (node (ref "SWITCH_M6") (pin "2") (pinfunction "2_2") (pintype "passive"))
      (node (ref "U2") (pin "7") (pinfunction "I/O[6]_7") (pintype "bidirectional"))
    )
    (net (code "28") (name "6_SX3") (class "Default")
      (node (ref "R29") (pin "1") (pinfunction "1_1") (pintype "passive"))
      (node (ref "SW1") (pin "19") (pinfunction "19_19") (pintype "passive"))
      (node (ref "U4") (pin "7") (pinfunction "I/O[6]_7") (pintype "bidirectional"))
    )
    (net (code "29") (name "7_SX1") (class "Default")
      (node (ref "R4") (pin "2") (pinfunction "2_2") (pintype "passive"))
      (node (ref "SWITCH_M4") (pin "2") (pinfunction "2_2") (pintype "passive"))
      (node (ref "U1") (pin "8") (pinfunction "I/O[7]_8") (pintype "bidirectional"))
    )
    (net (code "30") (name "7_SX2") (class "Default")
      (node (ref "R8") (pin "2") (pinfunction "2_2") (pintype "passive"))
      (node (ref "SWITCH_M8") (pin "2") (pinfunction "2_2") (pintype "passive"))
      (node (ref "U2") (pin "8") (pinfunction "I/O[7]_8") (pintype "bidirectional"))
    )
    (net (code "31") (name "7_SX3") (class "Default")
      (node (ref "R30") (pin "1") (pinfunction "1_1") (pintype "passive"))
      (node (ref "SW1") (pin "18") (pinfunction "18_18") (pintype "passive"))
      (node (ref "U4") (pin "8") (pinfunction "I/O[7]_8") (pintype "bidirectional"))
    )
    (net (code "32") (name "8_SX1") (class "Default")
      (node (ref "R1") (pin "2") (pinfunction "2_2") (pintype "passive"))
      (node (ref "SWITCH_M1") (pin "2") (pinfunction "2_2") (pintype "passive"))
      (node (ref "U1") (pin "13") (pinfunction "I/O[8]_13") (pintype "bidirectional"))
    )
    (net (code "33") (name "8_SX2") (class "Default")
      (node (ref "R5") (pin "2") (pinfunction "2_2") (pintype "passive"))
      (node (ref "SWITCH_M5") (pin "2") (pinfunction "2_2") (pintype "passive"))
      (node (ref "U2") (pin "13") (pinfunction "I/O[8]_13") (pintype "bidirectional"))
    )
    (net (code "34") (name "8_SX3") (class "Default")
      (node (ref "R31") (pin "1") (pinfunction "1_1") (pintype "passive"))
      (node (ref "SW1") (pin "17") (pinfunction "17_17") (pintype "passive"))
      (node (ref "U4") (pin "13") (pinfunction "I/O[8]_13") (pintype "bidirectional"))
    )
    (net (code "35") (name "9_SX1") (class "Default")
      (node (ref "R3") (pin "2") (pinfunction "2_2") (pintype "passive"))
      (node (ref "SWITCH_M3") (pin "2") (pinfunction "2_2") (pintype "passive"))
      (node (ref "U1") (pin "14") (pinfunction "I/O[9]_14") (pintype "bidirectional"))
    )
    (net (code "36") (name "9_SX2") (class "Default")
      (node (ref "R7") (pin "2") (pinfunction "2_2") (pintype "passive"))
      (node (ref "SWITCH_M7") (pin "2") (pinfunction "2_2") (pintype "passive"))
      (node (ref "U2") (pin "14") (pinfunction "I/O[9]_14") (pintype "bidirectional"))
    )
    (net (code "37") (name "9_SX3") (class "Default")
      (node (ref "R32") (pin "1") (pinfunction "1_1") (pintype "passive"))
      (node (ref "SW1") (pin "16") (pinfunction "16_16") (pintype "passive"))
      (node (ref "U4") (pin "14") (pinfunction "I/O[9]_14") (pintype "bidirectional"))
    )
    (net (code "38") (name "10_SX1") (class "Default")
      (node (ref "M_01") (pin "6") (pinfunction "6_6") (pintype "passive"))
      (node (ref "U1") (pin "15") (pinfunction "I/O[10]_15") (pintype "bidirectional"))
    )
    (net (code "39") (name "10_SX2") (class "Default")
      (node (ref "M_05") (pin "6") (pinfunction "6_6") (pintype "passive"))
      (node (ref "U2") (pin "15") (pinfunction "I/O[10]_15") (pintype "bidirectional"))
    )
    (net (code "40") (name "10_SX3") (class "Default")
      (node (ref "R33") (pin "1") (pinfunction "1_1") (pintype "passive"))
      (node (ref "SW1") (pin "15") (pinfunction "15_15") (pintype "passive"))
      (node (ref "U4") (pin "15") (pinfunction "I/O[10]_15") (pintype "bidirectional"))
    )
    (net (code "41") (name "11_SX1") (class "Default")
      (node (ref "M_01") (pin "5") (pinfunction "5_5") (pintype "passive"))
      (node (ref "U1") (pin "16") (pinfunction "I/O[11]_16") (pintype "bidirectional"))
    )
    (net (code "42") (name "11_SX2") (class "Default")
      (node (ref "M_05") (pin "5") (pinfunction "5_5") (pintype "passive"))
      (node (ref "U2") (pin "16") (pinfunction "I/O[11]_16") (pintype "bidirectional"))
    )
    (net (code "43") (name "11_SX3") (class "Default")
      (node (ref "R34") (pin "1") (pinfunction "1_1") (pintype "passive"))
      (node (ref "SW1") (pin "14") (pinfunction "14_14") (pintype "passive"))
      (node (ref "U4") (pin "16") (pinfunction "I/O[11]_16") (pintype "bidirectional"))
    )
    (net (code "44") (name "12_SX1") (class "Default")
      (node (ref "M_01") (pin "4") (pinfunction "4_4") (pintype "passive"))
      (node (ref "U1") (pin "19") (pinfunction "I/O[12]_19") (pintype "bidirectional"))
    )
    (net (code "45") (name "12_SX2") (class "Default")
      (node (ref "M_05") (pin "4") (pinfunction "4_4") (pintype "passive"))
      (node (ref "U2") (pin "19") (pinfunction "I/O[12]_19") (pintype "bidirectional"))
    )
    (net (code "46") (name "12_SX3") (class "Default")
      (node (ref "R35") (pin "1") (pinfunction "1_1") (pintype "passive"))
      (node (ref "SW1") (pin "13") (pinfunction "13_13") (pintype "passive"))
      (node (ref "U4") (pin "19") (pinfunction "I/O[12]_19") (pintype "bidirectional"))
    )
    (net (code "47") (name "13_SX1") (class "Default")
      (node (ref "M_03") (pin "6") (pinfunction "6_6") (pintype "passive"))
      (node (ref "U1") (pin "20") (pinfunction "I/O[13]_20") (pintype "bidirectional"))
    )
    (net (code "48") (name "13_SX2") (class "Default")
      (node (ref "M_07") (pin "6") (pinfunction "6_6") (pintype "passive"))
      (node (ref "U2") (pin "20") (pinfunction "I/O[13]_20") (pintype "bidirectional"))
    )
    (net (code "49") (name "13_SX3") (class "Default")
      (node (ref "R36") (pin "1") (pinfunction "1_1") (pintype "passive"))
      (node (ref "SW1") (pin "12") (pinfunction "12_12") (pintype "passive"))
      (node (ref "U4") (pin "20") (pinfunction "I/O[13]_20") (pintype "bidirectional"))
    )
    (net (code "50") (name "14_SX1") (class "Default")
      (node (ref "M_03") (pin "5") (pinfunction "5_5") (pintype "passive"))
      (node (ref "U1") (pin "21") (pinfunction "I/O[14]_21") (pintype "bidirectional"))
    )
    (net (code "51") (name "14_SX2") (class "Default")
      (node (ref "M_07") (pin "5") (pinfunction "5_5") (pintype "passive"))
      (node (ref "U2") (pin "21") (pinfunction "I/O[14]_21") (pintype "bidirectional"))
    )
    (net (code "52") (name "14_SX3") (class "Default")
      (node (ref "R37") (pin "1") (pinfunction "1_1") (pintype "passive"))
      (node (ref "SW1") (pin "11") (pinfunction "11_11") (pintype "passive"))
      (node (ref "U4") (pin "21") (pinfunction "I/O[14]_21") (pintype "bidirectional"))
    )
    (net (code "53") (name "15_SX1") (class "Default")
      (node (ref "M_03") (pin "4") (pinfunction "4_4") (pintype "passive"))
      (node (ref "U1") (pin "22") (pinfunction "I/O[15]_22") (pintype "bidirectional"))
    )
    (net (code "54") (name "15_SX2") (class "Default")
      (node (ref "M_07") (pin "4") (pinfunction "4_4") (pintype "passive"))
      (node (ref "U2") (pin "22") (pinfunction "I/O[15]_22") (pintype "bidirectional"))
    )
    (net (code "55") (name "15_SX3") (class "Default")
      (node (ref "R28") (pin "2") (pinfunction "2_2") (pintype "passive"))
      (node (ref "U4") (pin "22") (pinfunction "I/O[15]_22") (pintype "bidirectional"))
    )
    (net (code "56") (name "ADDR0_SX1") (class "Default")
      (node (ref "JP8") (pin "1") (pinfunction "1_1") (pintype "passive"))
      (node (ref "U1") (pin "26") (pinfunction "ADDR0_26") (pintype "bidirectional"))
    )
    (net (code "57") (name "ADDR0_SX2") (class "Default")
      (node (ref "JP7") (pin "1") (pinfunction "1_1") (pintype "passive"))
      (node (ref "U2") (pin "26") (pinfunction "ADDR0_26") (pintype "bidirectional"))
    )
    (net (code "58") (name "ADDR0_SX3") (class "Default")
      (node (ref "JP11") (pin "1") (pinfunction "1_1") (pintype "passive"))
      (node (ref "U4") (pin "26") (pinfunction "ADDR0_26") (pintype "bidirectional"))
    )
    (net (code "59") (name "ADDR1_SX1") (class "Default")
      (node (ref "JP9") (pin "1") (pinfunction "1_1") (pintype "passive"))
      (node (ref "U1") (pin "10") (pinfunction "ADDR1_10") (pintype "bidirectional"))
    )
    (net (code "60") (name "ADDR1_SX2") (class "Default")
      (node (ref "JP6") (pin "1") (pinfunction "1_1") (pintype "passive"))
      (node (ref "U2") (pin "10") (pinfunction "ADDR1_10") (pintype "bidirectional"))
    )
    (net (code "61") (name "ADDR1_SX3") (class "Default")
      (node (ref "JP10") (pin "1") (pinfunction "1_1") (pintype "passive"))
      (node (ref "U4") (pin "10") (pinfunction "ADDR1_10") (pintype "bidirectional"))
    )
    (net (code "62") (name "CAN_RX2") (class "Default")
      (node (ref "CONN01") (pin "4") (pinfunction "4_4") (pintype "bidirectional"))
      (node (ref "JP3") (pin "4") (pinfunction "4_4") (pintype "passive"))
    )
    (net (code "63") (name "CAN_TX2") (class "Default")
      (node (ref "CONN01") (pin "3") (pinfunction "3_3") (pintype "bidirectional"))
      (node (ref "JP3") (pin "3") (pinfunction "3_3") (pintype "passive"))
    )
    (net (code "64") (name "GND_MCU") (class "Default")
      (node (ref "C1") (pin "2") (pinfunction "2_2") (pintype "passive"))
      (node (ref "C2") (pin "2") (pinfunction "2_2") (pintype "passive"))
      (node (ref "C3") (pin "2") (pinfunction "2_2") (pintype "passive"))
      (node (ref "C4") (pin "2") (pinfunction "2_2") (pintype "passive"))
      (node (ref "C5") (pin "2") (pinfunction "2_2") (pintype "passive"))
      (node (ref "C6") (pin "2") (pinfunction "2_2") (pintype "passive"))
      (node (ref "C7") (pin "2") (pinfunction "2_2") (pintype "passive"))
      (node (ref "C8") (pin "2") (pinfunction "2_2") (pintype "passive"))
      (node (ref "C9") (pin "2") (pinfunction "2_2") (pintype "passive"))
      (node (ref "CONN01") (pin "11") (pinfunction "11_11") (pintype "bidirectional"))
      (node (ref "CONN01") (pin "9") (pinfunction "9_9") (pintype "bidirectional"))
      (node (ref "CONN02") (pin "11") (pinfunction "11_11") (pintype "bidirectional"))
      (node (ref "CONN02") (pin "9") (pinfunction "9_9") (pintype "bidirectional"))
      (node (ref "JP3") (pin "2") (pinfunction "2_2") (pintype "passive"))
      (node (ref "JP7") (pin "2") (pinfunction "2_2") (pintype "passive"))
      (node (ref "JP9") (pin "2") (pinfunction "2_2") (pintype "passive"))
      (node (ref "M_01") (pin "1") (pinfunction "1_1") (pintype "passive"))
      (node (ref "M_02") (pin "1") (pinfunction "1_1") (pintype "passive"))
      (node (ref "M_03") (pin "1") (pinfunction "1_1") (pintype "passive"))
      (node (ref "M_04") (pin "1") (pinfunction "1_1") (pintype "passive"))
      (node (ref "M_05") (pin "1") (pinfunction "1_1") (pintype "passive"))
      (node (ref "M_06") (pin "1") (pinfunction "1_1") (pintype "passive"))
      (node (ref "M_07") (pin "1") (pinfunction "1_1") (pintype "passive"))
      (node (ref "M_08") (pin "1") (pinfunction "1_1") (pintype "passive"))
      (node (ref "POWE_3.3") (pin "2") (pinfunction "C_2") (pintype "passive"))
      (node (ref "R1") (pin "1") (pinfunction "1_1") (pintype "passive"))
      (node (ref "R2") (pin "1") (pinfunction "1_1") (pintype "passive"))
      (node (ref "R22") (pin "1") (pinfunction "1_1") (pintype "passive"))
      (node (ref "R3") (pin "1") (pinfunction "1_1") (pintype "passive"))
      (node (ref "R4") (pin "1") (pinfunction "1_1") (pintype "passive"))
      (node (ref "R5") (pin "1") (pinfunction "1_1") (pintype "passive"))
      (node (ref "R6") (pin "1") (pinfunction "1_1") (pintype "passive"))
      (node (ref "R7") (pin "1") (pinfunction "1_1") (pintype "passive"))
      (node (ref "R8") (pin "1") (pinfunction "1_1") (pintype "passive"))
      (node (ref "STATUS_LED") (pin "2") (pinfunction "C_2") (pintype "passive"))
      (node (ref "SW1") (pin "1") (pinfunction "1_1") (pintype "passive"))
      (node (ref "SW1") (pin "10") (pinfunction "10_10") (pintype "passive"))
      (node (ref "SW1") (pin "2") (pinfunction "2_2") (pintype "passive"))
      (node (ref "SW1") (pin "3") (pinfunction "3_3") (pintype "passive"))
      (node (ref "SW1") (pin "4") (pinfunction "4_4") (pintype "passive"))
      (node (ref "SW1") (pin "5") (pinfunction "5_5") (pintype "passive"))
      (node (ref "SW1") (pin "6") (pinfunction "6_6") (pintype "passive"))
      (node (ref "SW1") (pin "7") (pinfunction "7_7") (pintype "passive"))
      (node (ref "SW1") (pin "8") (pinfunction "8_8") (pintype "passive"))
      (node (ref "SW1") (pin "9") (pinfunction "9_9") (pintype "passive"))
      (node (ref "U1") (pin "17") (pinfunction "GND_17") (pintype "bidirectional"))
      (node (ref "U1") (pin "29") (pinfunction "GND_29") (pintype "bidirectional"))
      (node (ref "U1") (pin "3") (pinfunction "GND_3") (pintype "bidirectional"))
      (node (ref "U2") (pin "17") (pinfunction "GND_17") (pintype "bidirectional"))
      (node (ref "U2") (pin "29") (pinfunction "GND_29") (pintype "bidirectional"))
      (node (ref "U2") (pin "3") (pinfunction "GND_3") (pintype "bidirectional"))
      (node (ref "U4") (pin "17") (pinfunction "GND_17") (pintype "bidirectional"))
      (node (ref "U4") (pin "29") (pinfunction "GND_29") (pintype "bidirectional"))
      (node (ref "U4") (pin "3") (pinfunction "GND_3") (pintype "bidirectional"))
    )
    (net (code "65") (name "NEOPIXEL_01") (class "Default")
      (node (ref "CONN02") (pin "2") (pinfunction "2_2") (pintype "bidirectional"))
      (node (ref "M_01") (pin "3") (pinfunction "3_3") (pintype "passive"))
    )
    (net (code "66") (name "NEOPIXEL_02") (class "Default")
      (node (ref "CONN02") (pin "1") (pinfunction "1_1") (pintype "bidirectional"))
      (node (ref "M_02") (pin "3") (pinfunction "3_3") (pintype "passive"))
    )
    (net (code "67") (name "NEOPIXEL_03") (class "Default")
      (node (ref "CONN02") (pin "4") (pinfunction "4_4") (pintype "bidirectional"))
      (node (ref "M_03") (pin "3") (pinfunction "3_3") (pintype "passive"))
    )
    (net (code "68") (name "NEOPIXEL_04") (class "Default")
      (node (ref "CONN02") (pin "3") (pinfunction "3_3") (pintype "bidirectional"))
      (node (ref "M_04") (pin "3") (pinfunction "3_3") (pintype "passive"))
    )
    (net (code "69") (name "NEOPIXEL_05") (class "Default")
      (node (ref "CONN02") (pin "6") (pinfunction "6_6") (pintype "bidirectional"))
      (node (ref "M_05") (pin "3") (pinfunction "3_3") (pintype "passive"))
    )
    (net (code "70") (name "NEOPIXEL_06") (class "Default")
      (node (ref "CONN02") (pin "5") (pinfunction "5_5") (pintype "bidirectional"))
      (node (ref "M_06") (pin "3") (pinfunction "3_3") (pintype "passive"))
    )
    (net (code "71") (name "NEOPIXEL_07") (class "Default")
      (node (ref "CONN02") (pin "8") (pinfunction "8_8") (pintype "bidirectional"))
      (node (ref "M_07") (pin "3") (pinfunction "3_3") (pintype "passive"))
    )
    (net (code "72") (name "NEOPIXEL_08") (class "Default")
      (node (ref "CONN02") (pin "7") (pinfunction "7_7") (pintype "bidirectional"))
      (node (ref "M_08") (pin "3") (pinfunction "3_3") (pintype "passive"))
    )
    (net (code "73") (name "Net-(JP6-Pad2)") (class "Default")
      (node (ref "JP6") (pin "2") (pinfunction "2_2") (pintype "passive"))
      (node (ref "R21") (pin "1") (pinfunction "1_1") (pintype "passive"))
    )
    (net (code "74") (name "Net-(JP8-Pad2)") (class "Default")
      (node (ref "JP8") (pin "2") (pinfunction "2_2") (pintype "passive"))
      (node (ref "R13") (pin "1") (pinfunction "1_1") (pintype "passive"))
    )
    (net (code "75") (name "Net-(JP10-Pad2)") (class "Default")
      (node (ref "JP10") (pin "2") (pinfunction "2_2") (pintype "passive"))
      (node (ref "R25") (pin "1") (pinfunction "1_1") (pintype "passive"))
    )
    (net (code "76") (name "Net-(JP11-Pad2)") (class "Default")
      (node (ref "JP11") (pin "2") (pinfunction "2_2") (pintype "passive"))
      (node (ref "R26") (pin "1") (pinfunction "1_1") (pintype "passive"))
    )
    (net (code "77") (name "Net-(POWE_3.3-A)") (class "Default")
      (node (ref "POWE_3.3") (pin "1") (pinfunction "A_1") (pintype "passive"))
      (node (ref "R27") (pin "1") (pinfunction "1_1") (pintype "passive"))
    )
    (net (code "78") (name "Net-(STATUS_LED-A)") (class "Default")
      (node (ref "R28") (pin "1") (pinfunction "1_1") (pintype "passive"))
      (node (ref "STATUS_LED") (pin "1") (pinfunction "A_1") (pintype "passive"))
    )
    (net (code "79") (name "OSCIO_SX1") (class "Default")
      (node (ref "U1") (pin "11") (pinfunction "OSCIO_11") (pintype "bidirectional"))
    )
    (net (code "80") (name "OSCIO_SX2") (class "Default")
      (node (ref "U2") (pin "11") (pinfunction "OSCIO_11") (pintype "bidirectional"))
    )
    (net (code "81") (name "OSCIO_SX3") (class "Default")
      (node (ref "U4") (pin "11") (pinfunction "OSCIO_11") (pintype "bidirectional"))
    )
    (net (code "82") (name "RX7") (class "Default")
      (node (ref "CONN01") (pin "6") (pinfunction "6_6") (pintype "bidirectional"))
      (node (ref "JP2") (pin "2") (pinfunction "2_2") (pintype "passive"))
    )
    (net (code "83") (name "SCL_00") (class "Default")
      (node (ref "CONN01") (pin "2") (pinfunction "2_2") (pintype "bidirectional"))
      (node (ref "R11") (pin "1") (pinfunction "1_1") (pintype "passive"))
      (node (ref "R18") (pin "1") (pinfunction "1_1") (pintype "passive"))
      (node (ref "R23") (pin "1") (pinfunction "1_1") (pintype "passive"))
      (node (ref "U1") (pin "25") (pinfunction "SCL_25") (pintype "bidirectional"))
      (node (ref "U2") (pin "25") (pinfunction "SCL_25") (pintype "bidirectional"))
      (node (ref "U4") (pin "25") (pinfunction "SCL_25") (pintype "bidirectional"))
    )
    (net (code "84") (name "SDA_00") (class "Default")
      (node (ref "CONN01") (pin "1") (pinfunction "1_1") (pintype "bidirectional"))
      (node (ref "R10") (pin "1") (pinfunction "1_1") (pintype "passive"))
      (node (ref "R17") (pin "1") (pinfunction "1_1") (pintype "passive"))
      (node (ref "R20") (pin "1") (pinfunction "1_1") (pintype "passive"))
      (node (ref "U1") (pin "24") (pinfunction "SDA_24") (pintype "bidirectional"))
      (node (ref "U2") (pin "24") (pinfunction "SDA_24") (pintype "bidirectional"))
      (node (ref "U4") (pin "24") (pinfunction "SDA_24") (pintype "bidirectional"))
    )
    (net (code "85") (name "TX7") (class "Default")
      (node (ref "CONN01") (pin "5") (pinfunction "5_5") (pintype "bidirectional"))
      (node (ref "JP2") (pin "1") (pinfunction "1_1") (pintype "passive"))
    )
    (net (code "86") (name "VCC_5V") (class "Default")
      (node (ref "M_01") (pin "2") (pinfunction "2_2") (pintype "passive"))
      (node (ref "M_02") (pin "2") (pinfunction "2_2") (pintype "passive"))
      (node (ref "M_03") (pin "2") (pinfunction "2_2") (pintype "passive"))
      (node (ref "M_04") (pin "2") (pinfunction "2_2") (pintype "passive"))
      (node (ref "M_05") (pin "2") (pinfunction "2_2") (pintype "passive"))
      (node (ref "M_06") (pin "2") (pinfunction "2_2") (pintype "passive"))
      (node (ref "M_07") (pin "2") (pinfunction "2_2") (pintype "passive"))
      (node (ref "M_08") (pin "2") (pinfunction "2_2") (pintype "passive"))
      (node (ref "S1") (pin "2") (pinfunction "2_2") (pintype "passive"))
    )
    (net (code "87") (name "VCC_5V_IN") (class "Default")
      (node (ref "CONN01") (pin "12") (pinfunction "12_12") (pintype "bidirectional"))
      (node (ref "CONN02") (pin "12") (pinfunction "12_12") (pintype "bidirectional"))
      (node (ref "S1") (pin "3") (pinfunction "3_3") (pintype "passive"))
    )
    (net (code "88") (name "unconnected-(S1-Pad1)") (class "Default")
      (node (ref "S1") (pin "1") (pinfunction "1_1") (pintype "passive"))
    )
    (net (code "89") (name "unconnected-(S1-Pad4)") (class "Default")
      (node (ref "S1") (pin "4") (pinfunction "4_4") (pintype "passive"))
    )
    (net (code "90") (name "unconnected-(S1-Pad5)") (class "Default")
      (node (ref "S1") (pin "5") (pinfunction "5_5") (pintype "passive"))
    )
    (net (code "91") (name "unconnected-(S1-Pad6)") (class "Default")
      (node (ref "S1") (pin "6") (pinfunction "6_6") (pintype "passive"))
    )
    (net (code "92") (name "unconnected-(S1-Pad7)") (class "Default")
      (node (ref "S1") (pin "7") (pinfunction "7_7") (pintype "passive"))
    )
    (net (code "93") (name "unconnected-(S1-Pad8)") (class "Default")
      (node (ref "S1") (pin "8") (pinfunction "8_8") (pintype "passive"))
    )
  )
)
